# Connector.net
KiCad netlist of a schematic drawn in Altium Designer
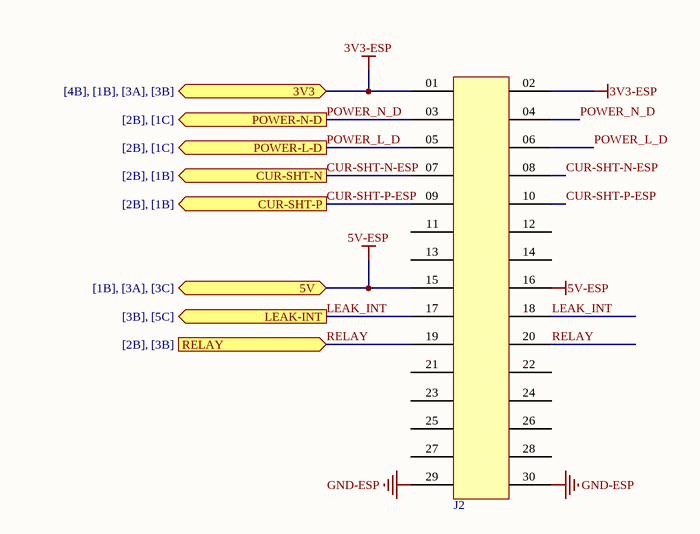
[diagram p0: Connector.SchDoc]

(export (version "E")
  (design (tool "Eeschema 10.0.6"))
  (components
    (comp (ref "J2")
      (value "HEADER; 15x2PIN; 2.54; HOR;")
      (footprint "HEADER-2.54-15x2-HOR-U3D")
      (fields (field (name "DESIGNER") "TVBac"))
      (libsource (lib "Socket") (part "HEADER; 15x2PIN; 2.54; HOR;"))
    )
  )
  (nets
    (net (code "1") (name "/CUR-SHT-N-ESP") (class "Default")
      (node (ref "J2") (pin "07") (pinfunction "07_07") (pintype "passive"))
      (node (ref "J2") (pin "08") (pinfunction "08_08") (pintype "passive"))
    )
    (net (code "2") (name "/CUR-SHT-P-ESP") (class "Default")
      (node (ref "J2") (pin "09") (pinfunction "09_09") (pintype "passive"))
      (node (ref "J2") (pin "10") (pinfunction "10_10") (pintype "passive"))
    )
    (net (code "3") (name "/LEAK_INT") (class "Default")
      (node (ref "J2") (pin "17") (pinfunction "17_17") (pintype "passive"))
      (node (ref "J2") (pin "18") (pinfunction "18_18") (pintype "passive"))
    )
    (net (code "4") (name "/POWER_L_D") (class "Default")
      (node (ref "J2") (pin "05") (pinfunction "05_05") (pintype "passive"))
      (node (ref "J2") (pin "06") (pinfunction "06_06") (pintype "passive"))
    )
    (net (code "5") (name "/POWER_N_D") (class "Default")
      (node (ref "J2") (pin "03") (pinfunction "03_03") (pintype "passive"))
      (node (ref "J2") (pin "04") (pinfunction "04_04") (pintype "passive"))
    )
    (net (code "6") (name "/RELAY") (class "Default")
      (node (ref "J2") (pin "19") (pinfunction "19_19") (pintype "passive"))
      (node (ref "J2") (pin "20") (pinfunction "20_20") (pintype "passive"))
    )
    (net (code "7") (name "3V3-ESP") (class "Default")
      (node (ref "J2") (pin "01") (pinfunction "01_01") (pintype "passive"))
      (node (ref "J2") (pin "02") (pinfunction "02_02") (pintype "passive"))
    )
    (net (code "8") (name "5V-ESP") (class "Default")
      (node (ref "J2") (pin "15") (pinfunction "15_15") (pintype "passive"))
      (node (ref "J2") (pin "16") (pinfunction "16_16") (pintype "passive"))
    )
    (net (code "9") (name "GND-ESP") (class "Default")
      (node (ref "J2") (pin "29") (pinfunction "29_29") (pintype "passive"))
      (node (ref "J2") (pin "30") (pinfunction "30_30") (pintype "passive"))
    )
    (net (code "10") (name "unconnected-(J2-Pad11)") (class "Default")
      (node (ref "J2") (pin "11") (pinfunction "11_11") (pintype "passive"))
    )
    (net (code "11") (name "unconnected-(J2-Pad12)") (class "Default")
      (node (ref "J2") (pin "12") (pinfunction "12_12") (pintype "passive"))
    )
    (net (code "12") (name "unconnected-(J2-Pad13)") (class "Default")
      (node (ref "J2") (pin "13") (pinfunction "13_13") (pintype "passive"))
    )
    (net (code "13") (name "unconnected-(J2-Pad14)") (class "Default")
      (node (ref "J2") (pin "14") (pinfunction "14_14") (pintype "passive"))
    )
    (net (code "14") (name "unconnected-(J2-Pad21)") (class "Default")
      (node (ref "J2") (pin "21") (pinfunction "21_21") (pintype "passive"))
    )
    (net (code "15") (name "unconnected-(J2-Pad22)") (class "Default")
      (node (ref "J2") (pin "22") (pinfunction "22_22") (pintype "passive"))
    )
    (net (code "16") (name "unconnected-(J2-Pad23)") (class "Default")
      (node (ref "J2") (pin "23") (pinfunction "23_23") (pintype "passive"))
    )
    (net (code "17") (name "unconnected-(J2-Pad24)") (class "Default")
      (node (ref "J2") (pin "24") (pinfunction "24_24") (pintype "passive"))
    )
    (net (code "18") (name "unconnected-(J2-Pad25)") (class "Default")
      (node (ref "J2") (pin "25") (pinfunction "25_25") (pintype "passive"))
    )
    (net (code "19") (name "unconnected-(J2-Pad26)") (class "Default")
      (node (ref "J2") (pin "26") (pinfunction "26_26") (pintype "passive"))
    )
    (net (code "20") (name "unconnected-(J2-Pad27)") (class "Default")
      (node (ref "J2") (pin "27") (pinfunction "27_27") (pintype "passive"))
    )
    (net (code "21") (name "unconnected-(J2-Pad28)") (class "Default")
      (node (ref "J2") (pin "28") (pinfunction "28_28") (pintype "passive"))
    )
  )
)
